# E70_AND_E79.net
KiCad netlist of a schematic drawn in Altium Designer
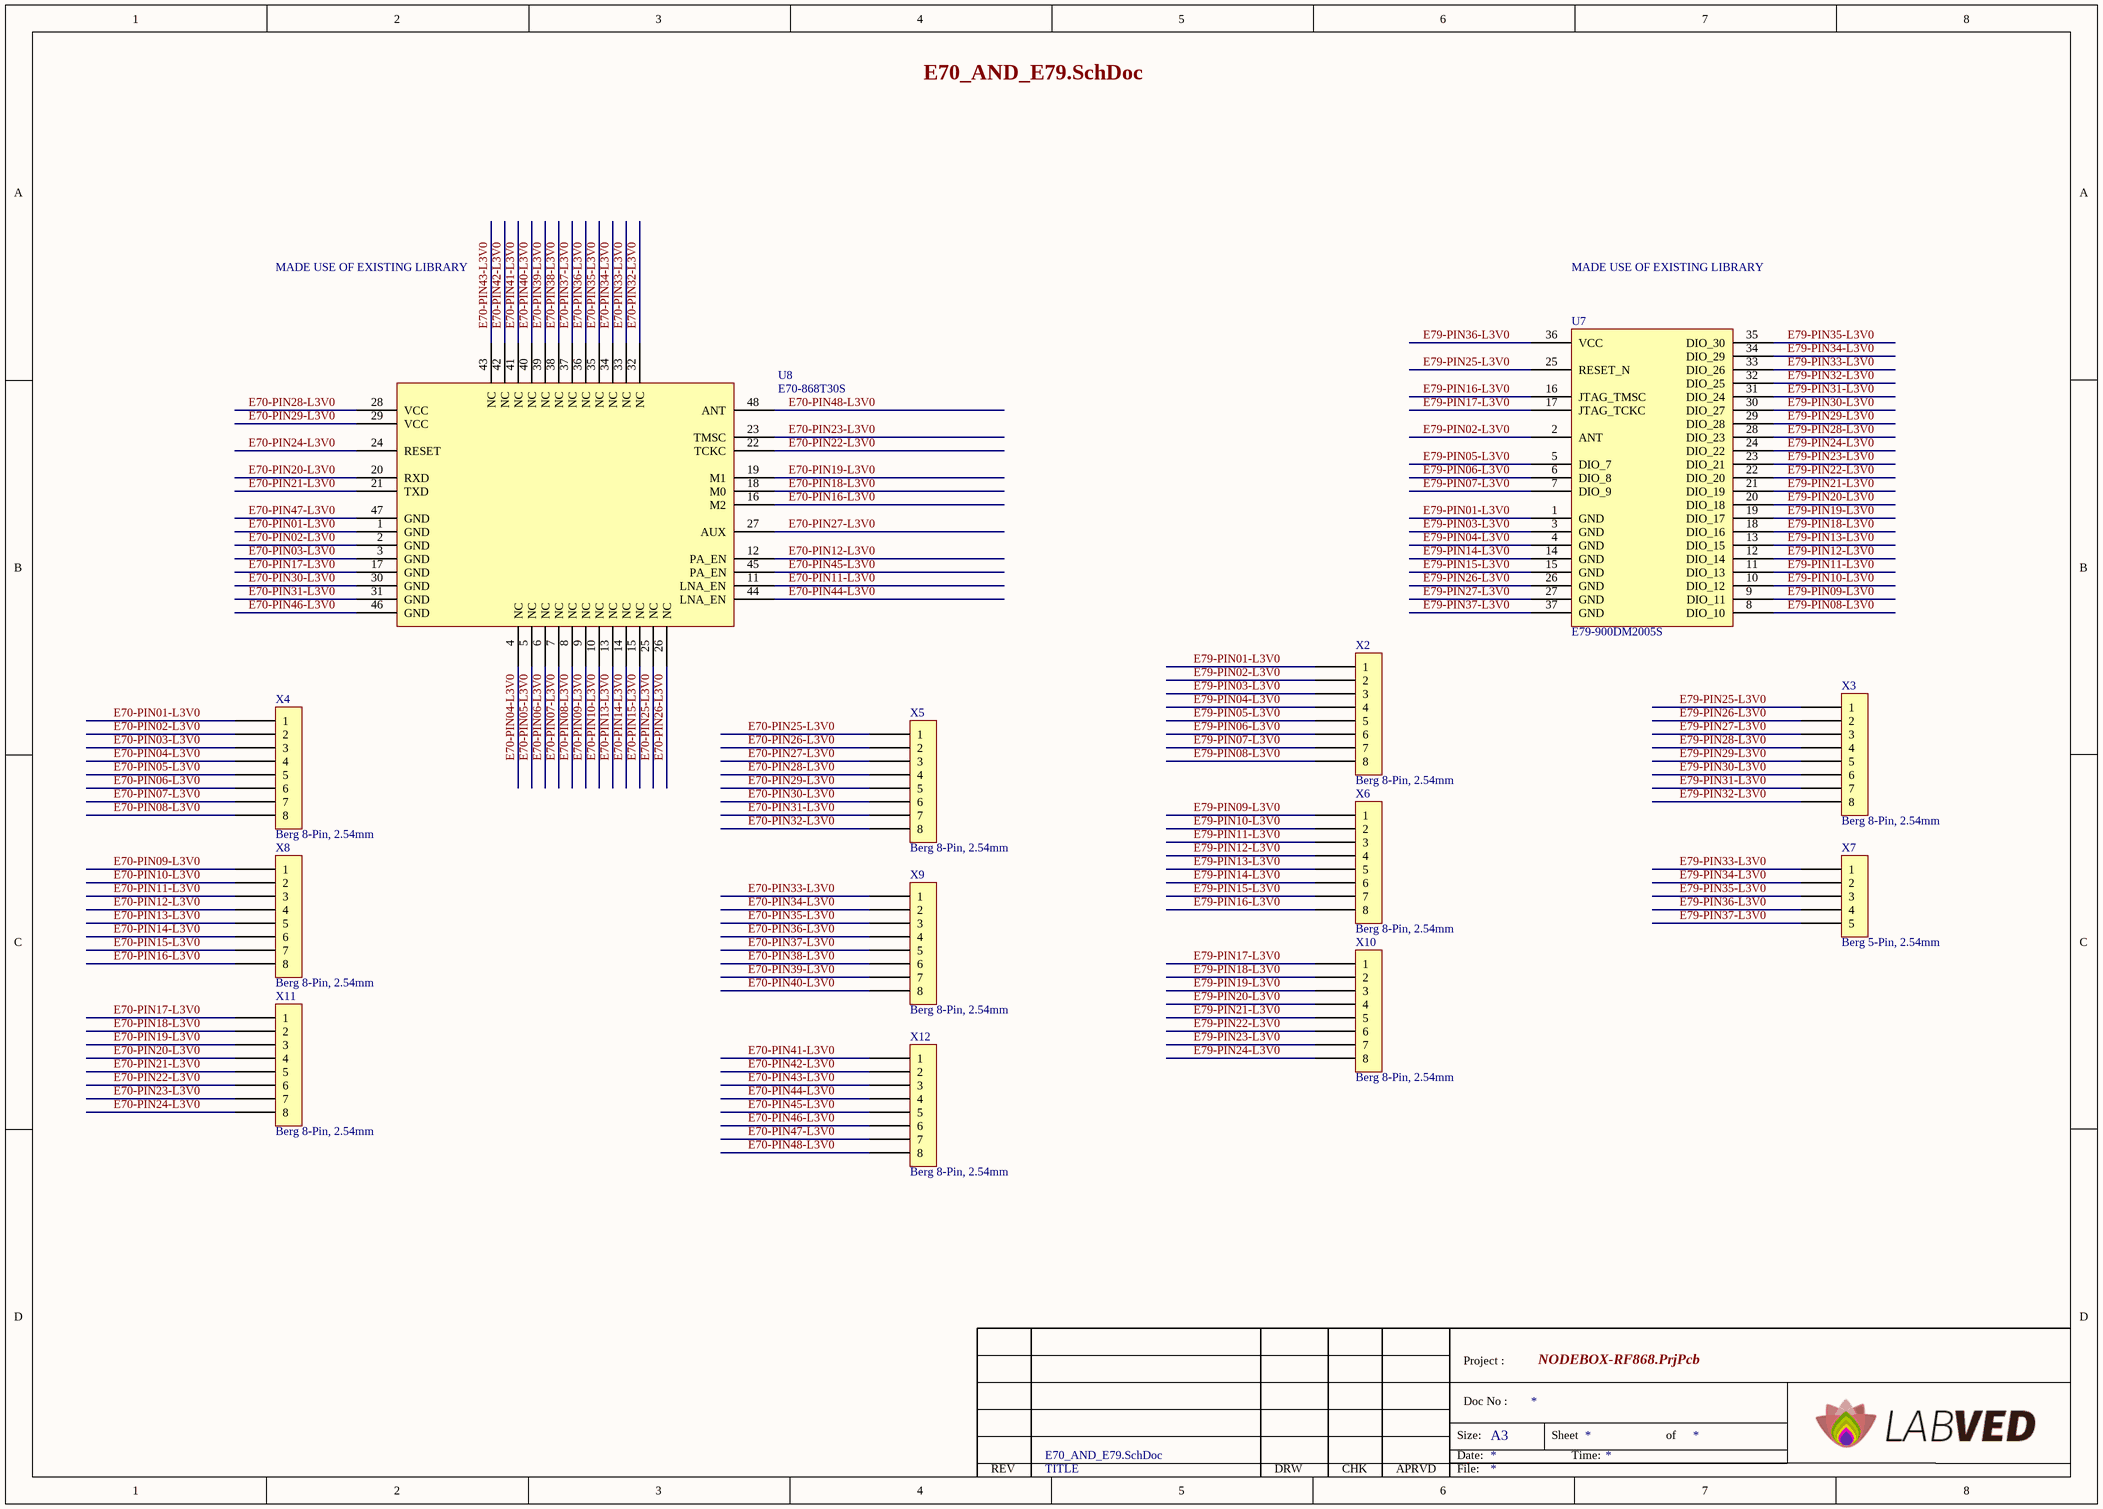
[diagram p0: E70_AND_E79.SchDoc]

(export (version "E")
  (design (tool "Eeschema 10.0.6"))
  (components
    (comp (ref "U7")
      (value "E79-900DM2005S")
      (footprint "E79-900DM2005S")
      (description "LORA MODULE")
      (libsource (lib "<Company> Vault") (part "E79-900DM2005S"))
    )
    (comp (ref "U8")
      (value "E70-868T30S")
      (footprint "E70-868T30S")
      (description "WIRELESS LORA MODULE")
      (libsource (lib "<Company> Vault") (part "E70-868T30S"))
    )
    (comp (ref "X2")
      (value "Berg 8-Pin, 2.54mm")
      (footprint "Berg 8-Pin, 2.54MM")
      (description "Berg 8-Pin, 2.54mm pitch")
      (libsource (lib "<Company> Vault") (part "Barrier Terminal Block, 8-Pin 8.25mm"))
    )
    (comp (ref "X3")
      (value "Berg 8-Pin, 2.54mm")
      (footprint "Berg 8-Pin, 2.54MM")
      (description "Berg 8-Pin, 2.54mm pitch")
      (libsource (lib "<Company> Vault") (part "Barrier Terminal Block, 8-Pin 8.25mm"))
    )
    (comp (ref "X4")
      (value "Berg 8-Pin, 2.54mm")
      (footprint "Berg 8-Pin, 2.54MM")
      (description "Berg 8-Pin, 2.54mm pitch")
      (libsource (lib "<Company> Vault") (part "Barrier Terminal Block, 8-Pin 8.25mm"))
    )
    (comp (ref "X5")
      (value "Berg 8-Pin, 2.54mm")
      (footprint "Berg 8-Pin, 2.54MM")
      (description "Berg 8-Pin, 2.54mm pitch")
      (libsource (lib "<Company> Vault") (part "Barrier Terminal Block, 8-Pin 8.25mm"))
    )
    (comp (ref "X6")
      (value "Berg 8-Pin, 2.54mm")
      (footprint "Berg 8-Pin, 2.54MM")
      (description "Berg 8-Pin, 2.54mm pitch")
      (libsource (lib "<Company> Vault") (part "Barrier Terminal Block, 8-Pin 8.25mm"))
    )
    (comp (ref "X7")
      (value "Berg 5-Pin, 2.54mm")
      (footprint "Berg 5-Pin, 2.54MM")
      (description "Berg 5-Pin, 2.54mm pitch")
      (libsource (lib "<Company> Vault") (part "Berg 5-Pin, 2.54mm"))
    )
    (comp (ref "X8")
      (value "Berg 8-Pin, 2.54mm")
      (footprint "Berg 8-Pin, 2.54MM")
      (description "Berg 8-Pin, 2.54mm pitch")
      (libsource (lib "<Company> Vault") (part "Barrier Terminal Block, 8-Pin 8.25mm"))
    )
    (comp (ref "X9")
      (value "Berg 8-Pin, 2.54mm")
      (footprint "Berg 8-Pin, 2.54MM")
      (description "Berg 8-Pin, 2.54mm pitch")
      (libsource (lib "<Company> Vault") (part "Barrier Terminal Block, 8-Pin 8.25mm"))
    )
    (comp (ref "X10")
      (value "Berg 8-Pin, 2.54mm")
      (footprint "Berg 8-Pin, 2.54MM")
      (description "Berg 8-Pin, 2.54mm pitch")
      (libsource (lib "<Company> Vault") (part "Barrier Terminal Block, 8-Pin 8.25mm"))
    )
    (comp (ref "X11")
      (value "Berg 8-Pin, 2.54mm")
      (footprint "Berg 8-Pin, 2.54MM")
      (description "Berg 8-Pin, 2.54mm pitch")
      (libsource (lib "<Company> Vault") (part "Barrier Terminal Block, 8-Pin 8.25mm"))
    )
    (comp (ref "X12")
      (value "Berg 8-Pin, 2.54mm")
      (footprint "Berg 8-Pin, 2.54MM")
      (description "Berg 8-Pin, 2.54mm pitch")
      (libsource (lib "<Company> Vault") (part "Barrier Terminal Block, 8-Pin 8.25mm"))
    )
  )
  (nets
    (net (code "1") (name "/E70-PIN01-L3V0") (class "Default")
      (node (ref "U8") (pin "1") (pinfunction "GND_1") (pintype "passive"))
      (node (ref "X4") (pin "1") (pinfunction "1_1") (pintype "passive"))
    )
    (net (code "2") (name "/E70-PIN02-L3V0") (class "Default")
      (node (ref "U8") (pin "2") (pinfunction "GND_2") (pintype "passive"))
      (node (ref "X4") (pin "2") (pinfunction "2_2") (pintype "passive"))
    )
    (net (code "3") (name "/E70-PIN03-L3V0") (class "Default")
      (node (ref "U8") (pin "3") (pinfunction "GND_3") (pintype "passive"))
      (node (ref "X4") (pin "3") (pinfunction "3_3") (pintype "passive"))
    )
    (net (code "4") (name "/E70-PIN04-L3V0") (class "Default")
      (node (ref "U8") (pin "4") (pinfunction "NC_4") (pintype "passive"))
      (node (ref "X4") (pin "4") (pinfunction "4_4") (pintype "passive"))
    )
    (net (code "5") (name "/E70-PIN05-L3V0") (class "Default")
      (node (ref "U8") (pin "5") (pinfunction "NC_5") (pintype "passive"))
      (node (ref "X4") (pin "5") (pinfunction "5_5") (pintype "passive"))
    )
    (net (code "6") (name "/E70-PIN06-L3V0") (class "Default")
      (node (ref "U8") (pin "6") (pinfunction "NC_6") (pintype "passive"))
      (node (ref "X4") (pin "6") (pinfunction "6_6") (pintype "passive"))
    )
    (net (code "7") (name "/E70-PIN07-L3V0") (class "Default")
      (node (ref "U8") (pin "7") (pinfunction "NC_7") (pintype "passive"))
      (node (ref "X4") (pin "7") (pinfunction "7_7") (pintype "passive"))
    )
    (net (code "8") (name "/E70-PIN08-L3V0") (class "Default")
      (node (ref "U8") (pin "8") (pinfunction "NC_8") (pintype "passive"))
      (node (ref "X4") (pin "8") (pinfunction "8_8") (pintype "passive"))
    )
    (net (code "9") (name "/E70-PIN09-L3V0") (class "Default")
      (node (ref "U8") (pin "9") (pinfunction "NC_9") (pintype "passive"))
      (node (ref "X8") (pin "1") (pinfunction "1_1") (pintype "passive"))
    )
    (net (code "10") (name "/E70-PIN10-L3V0") (class "Default")
      (node (ref "U8") (pin "10") (pinfunction "NC_10") (pintype "passive"))
      (node (ref "X8") (pin "2") (pinfunction "2_2") (pintype "passive"))
    )
    (net (code "11") (name "/E70-PIN11-L3V0") (class "Default")
      (node (ref "U8") (pin "11") (pinfunction "LNA_EN_11") (pintype "passive"))
      (node (ref "X8") (pin "3") (pinfunction "3_3") (pintype "passive"))
    )
    (net (code "12") (name "/E70-PIN12-L3V0") (class "Default")
      (node (ref "U8") (pin "12") (pinfunction "PA_EN_12") (pintype "passive"))
      (node (ref "X8") (pin "4") (pinfunction "4_4") (pintype "passive"))
    )
    (net (code "13") (name "/E70-PIN13-L3V0") (class "Default")
      (node (ref "U8") (pin "13") (pinfunction "NC_13") (pintype "passive"))
      (node (ref "X8") (pin "5") (pinfunction "5_5") (pintype "passive"))
    )
    (net (code "14") (name "/E70-PIN14-L3V0") (class "Default")
      (node (ref "U8") (pin "14") (pinfunction "NC_14") (pintype "passive"))
      (node (ref "X8") (pin "6") (pinfunction "6_6") (pintype "passive"))
    )
    (net (code "15") (name "/E70-PIN15-L3V0") (class "Default")
      (node (ref "U8") (pin "15") (pinfunction "NC_15") (pintype "passive"))
      (node (ref "X8") (pin "7") (pinfunction "7_7") (pintype "passive"))
    )
    (net (code "16") (name "/E70-PIN16-L3V0") (class "Default")
      (node (ref "U8") (pin "16") (pinfunction "M2_16") (pintype "passive"))
      (node (ref "X8") (pin "8") (pinfunction "8_8") (pintype "passive"))
    )
    (net (code "17") (name "/E70-PIN17-L3V0") (class "Default")
      (node (ref "U8") (pin "17") (pinfunction "GND_17") (pintype "passive"))
      (node (ref "X11") (pin "1") (pinfunction "1_1") (pintype "passive"))
    )
    (net (code "18") (name "/E70-PIN18-L3V0") (class "Default")
      (node (ref "U8") (pin "18") (pinfunction "M0_18") (pintype "passive"))
      (node (ref "X11") (pin "2") (pinfunction "2_2") (pintype "passive"))
    )
    (net (code "19") (name "/E70-PIN19-L3V0") (class "Default")
      (node (ref "U8") (pin "19") (pinfunction "M1_19") (pintype "passive"))
      (node (ref "X11") (pin "3") (pinfunction "3_3") (pintype "passive"))
    )
    (net (code "20") (name "/E70-PIN20-L3V0") (class "Default")
      (node (ref "U8") (pin "20") (pinfunction "RXD_20") (pintype "passive"))
      (node (ref "X11") (pin "4") (pinfunction "4_4") (pintype "passive"))
    )
    (net (code "21") (name "/E70-PIN21-L3V0") (class "Default")
      (node (ref "U8") (pin "21") (pinfunction "TXD_21") (pintype "passive"))
      (node (ref "X11") (pin "5") (pinfunction "5_5") (pintype "passive"))
    )
    (net (code "22") (name "/E70-PIN22-L3V0") (class "Default")
      (node (ref "U8") (pin "22") (pinfunction "TCKC_22") (pintype "passive"))
      (node (ref "X11") (pin "6") (pinfunction "6_6") (pintype "passive"))
    )
    (net (code "23") (name "/E70-PIN23-L3V0") (class "Default")
      (node (ref "U8") (pin "23") (pinfunction "TMSC_23") (pintype "passive"))
      (node (ref "X11") (pin "7") (pinfunction "7_7") (pintype "passive"))
    )
    (net (code "24") (name "/E70-PIN24-L3V0") (class "Default")
      (node (ref "U8") (pin "24") (pinfunction "RESET_24") (pintype "passive"))
      (node (ref "X11") (pin "8") (pinfunction "8_8") (pintype "passive"))
    )
    (net (code "25") (name "/E70-PIN25-L3V0") (class "Default")
      (node (ref "U8") (pin "25") (pinfunction "NC_25") (pintype "passive"))
      (node (ref "X5") (pin "1") (pinfunction "1_1") (pintype "passive"))
    )
    (net (code "26") (name "/E70-PIN26-L3V0") (class "Default")
      (node (ref "U8") (pin "26") (pinfunction "NC_26") (pintype "passive"))
      (node (ref "X5") (pin "2") (pinfunction "2_2") (pintype "passive"))
    )
    (net (code "27") (name "/E70-PIN27-L3V0") (class "Default")
      (node (ref "U8") (pin "27") (pinfunction "AUX_27") (pintype "passive"))
      (node (ref "X5") (pin "3") (pinfunction "3_3") (pintype "passive"))
    )
    (net (code "28") (name "/E70-PIN28-L3V0") (class "Default")
      (node (ref "U8") (pin "28") (pinfunction "VCC_28") (pintype "passive"))
      (node (ref "X5") (pin "4") (pinfunction "4_4") (pintype "passive"))
    )
    (net (code "29") (name "/E70-PIN29-L3V0") (class "Default")
      (node (ref "U8") (pin "29") (pinfunction "VCC_29") (pintype "passive"))
      (node (ref "X5") (pin "5") (pinfunction "5_5") (pintype "passive"))
    )
    (net (code "30") (name "/E70-PIN30-L3V0") (class "Default")
      (node (ref "U8") (pin "30") (pinfunction "GND_30") (pintype "passive"))
      (node (ref "X5") (pin "6") (pinfunction "6_6") (pintype "passive"))
    )
    (net (code "31") (name "/E70-PIN31-L3V0") (class "Default")
      (node (ref "U8") (pin "31") (pinfunction "GND_31") (pintype "passive"))
      (node (ref "X5") (pin "7") (pinfunction "7_7") (pintype "passive"))
    )
    (net (code "32") (name "/E70-PIN32-L3V0") (class "Default")
      (node (ref "U8") (pin "32") (pinfunction "NC_32") (pintype "passive"))
      (node (ref "X5") (pin "8") (pinfunction "8_8") (pintype "passive"))
    )
    (net (code "33") (name "/E70-PIN33-L3V0") (class "Default")
      (node (ref "U8") (pin "33") (pinfunction "NC_33") (pintype "passive"))
      (node (ref "X9") (pin "1") (pinfunction "1_1") (pintype "passive"))
    )
    (net (code "34") (name "/E70-PIN34-L3V0") (class "Default")
      (node (ref "U8") (pin "34") (pinfunction "NC_34") (pintype "passive"))
      (node (ref "X9") (pin "2") (pinfunction "2_2") (pintype "passive"))
    )
    (net (code "35") (name "/E70-PIN35-L3V0") (class "Default")
      (node (ref "U8") (pin "35") (pinfunction "NC_35") (pintype "passive"))
      (node (ref "X9") (pin "3") (pinfunction "3_3") (pintype "passive"))
    )
    (net (code "36") (name "/E70-PIN36-L3V0") (class "Default")
      (node (ref "U8") (pin "36") (pinfunction "NC_36") (pintype "passive"))
      (node (ref "X9") (pin "4") (pinfunction "4_4") (pintype "passive"))
    )
    (net (code "37") (name "/E70-PIN37-L3V0") (class "Default")
      (node (ref "U8") (pin "37") (pinfunction "NC_37") (pintype "passive"))
      (node (ref "X9") (pin "5") (pinfunction "5_5") (pintype "passive"))
    )
    (net (code "38") (name "/E70-PIN38-L3V0") (class "Default")
      (node (ref "U8") (pin "38") (pinfunction "NC_38") (pintype "passive"))
      (node (ref "X9") (pin "6") (pinfunction "6_6") (pintype "passive"))
    )
    (net (code "39") (name "/E70-PIN39-L3V0") (class "Default")
      (node (ref "U8") (pin "39") (pinfunction "NC_39") (pintype "passive"))
      (node (ref "X9") (pin "7") (pinfunction "7_7") (pintype "passive"))
    )
    (net (code "40") (name "/E70-PIN40-L3V0") (class "Default")
      (node (ref "U8") (pin "40") (pinfunction "NC_40") (pintype "passive"))
      (node (ref "X9") (pin "8") (pinfunction "8_8") (pintype "passive"))
    )
    (net (code "41") (name "/E70-PIN41-L3V0") (class "Default")
      (node (ref "U8") (pin "41") (pinfunction "NC_41") (pintype "passive"))
      (node (ref "X12") (pin "1") (pinfunction "1_1") (pintype "passive"))
    )
    (net (code "42") (name "/E70-PIN42-L3V0") (class "Default")
      (node (ref "U8") (pin "42") (pinfunction "NC_42") (pintype "passive"))
      (node (ref "X12") (pin "2") (pinfunction "2_2") (pintype "passive"))
    )
    (net (code "43") (name "/E70-PIN43-L3V0") (class "Default")
      (node (ref "U8") (pin "43") (pinfunction "NC_43") (pintype "passive"))
      (node (ref "X12") (pin "3") (pinfunction "3_3") (pintype "passive"))
    )
    (net (code "44") (name "/E70-PIN44-L3V0") (class "Default")
      (node (ref "U8") (pin "44") (pinfunction "LNA_EN_44") (pintype "passive"))
      (node (ref "X12") (pin "4") (pinfunction "4_4") (pintype "passive"))
    )
    (net (code "45") (name "/E70-PIN45-L3V0") (class "Default")
      (node (ref "U8") (pin "45") (pinfunction "PA_EN_45") (pintype "passive"))
      (node (ref "X12") (pin "5") (pinfunction "5_5") (pintype "passive"))
    )
    (net (code "46") (name "/E70-PIN46-L3V0") (class "Default")
      (node (ref "U8") (pin "46") (pinfunction "GND_46") (pintype "passive"))
      (node (ref "X12") (pin "6") (pinfunction "6_6") (pintype "passive"))
    )
    (net (code "47") (name "/E70-PIN47-L3V0") (class "Default")
      (node (ref "U8") (pin "47") (pinfunction "GND_47") (pintype "passive"))
      (node (ref "X12") (pin "7") (pinfunction "7_7") (pintype "passive"))
    )
    (net (code "48") (name "/E70-PIN48-L3V0") (class "Default")
      (node (ref "U8") (pin "48") (pinfunction "ANT_48") (pintype "passive"))
      (node (ref "X12") (pin "8") (pinfunction "8_8") (pintype "passive"))
    )
    (net (code "49") (name "/E79-PIN01-L3V0") (class "Default")
      (node (ref "U7") (pin "1") (pinfunction "GND_1") (pintype "passive"))
      (node (ref "X2") (pin "1") (pinfunction "1_1") (pintype "passive"))
    )
    (net (code "50") (name "/E79-PIN02-L3V0") (class "Default")
      (node (ref "U7") (pin "2") (pinfunction "ANT_2") (pintype "passive"))
      (node (ref "X2") (pin "2") (pinfunction "2_2") (pintype "passive"))
    )
    (net (code "51") (name "/E79-PIN03-L3V0") (class "Default")
      (node (ref "U7") (pin "3") (pinfunction "GND_3") (pintype "passive"))
      (node (ref "X2") (pin "3") (pinfunction "3_3") (pintype "passive"))
    )
    (net (code "52") (name "/E79-PIN04-L3V0") (class "Default")
      (node (ref "U7") (pin "4") (pinfunction "GND_4") (pintype "passive"))
      (node (ref "X2") (pin "4") (pinfunction "4_4") (pintype "passive"))
    )
    (net (code "53") (name "/E79-PIN05-L3V0") (class "Default")
      (node (ref "U7") (pin "5") (pinfunction "DIO_7_5") (pintype "passive"))
      (node (ref "X2") (pin "5") (pinfunction "5_5") (pintype "passive"))
    )
    (net (code "54") (name "/E79-PIN06-L3V0") (class "Default")
      (node (ref "U7") (pin "6") (pinfunction "DIO_8_6") (pintype "passive"))
      (node (ref "X2") (pin "6") (pinfunction "6_6") (pintype "passive"))
    )
    (net (code "55") (name "/E79-PIN07-L3V0") (class "Default")
      (node (ref "U7") (pin "7") (pinfunction "DIO_9_7") (pintype "passive"))
      (node (ref "X2") (pin "7") (pinfunction "7_7") (pintype "passive"))
    )
    (net (code "56") (name "/E79-PIN08-L3V0") (class "Default")
      (node (ref "U7") (pin "8") (pinfunction "DIO_10_8") (pintype "passive"))
      (node (ref "X2") (pin "8") (pinfunction "8_8") (pintype "passive"))
    )
    (net (code "57") (name "/E79-PIN09-L3V0") (class "Default")
      (node (ref "U7") (pin "9") (pinfunction "DIO_11_9") (pintype "passive"))
      (node (ref "X6") (pin "1") (pinfunction "1_1") (pintype "passive"))
    )
    (net (code "58") (name "/E79-PIN10-L3V0") (class "Default")
      (node (ref "U7") (pin "10") (pinfunction "DIO_12_10") (pintype "passive"))
      (node (ref "X6") (pin "2") (pinfunction "2_2") (pintype "passive"))
    )
    (net (code "59") (name "/E79-PIN11-L3V0") (class "Default")
      (node (ref "U7") (pin "11") (pinfunction "DIO_13_11") (pintype "passive"))
      (node (ref "X6") (pin "3") (pinfunction "3_3") (pintype "passive"))
    )
    (net (code "60") (name "/E79-PIN12-L3V0") (class "Default")
      (node (ref "U7") (pin "12") (pinfunction "DIO_14_12") (pintype "passive"))
      (node (ref "X6") (pin "4") (pinfunction "4_4") (pintype "passive"))
    )
    (net (code "61") (name "/E79-PIN13-L3V0") (class "Default")
      (node (ref "U7") (pin "13") (pinfunction "DIO_15_13") (pintype "passive"))
      (node (ref "X6") (pin "5") (pinfunction "5_5") (pintype "passive"))
    )
    (net (code "62") (name "/E79-PIN14-L3V0") (class "Default")
      (node (ref "U7") (pin "14") (pinfunction "GND_14") (pintype "passive"))
      (node (ref "X6") (pin "6") (pinfunction "6_6") (pintype "passive"))
    )
    (net (code "63") (name "/E79-PIN15-L3V0") (class "Default")
      (node (ref "U7") (pin "15") (pinfunction "GND_15") (pintype "passive"))
      (node (ref "X6") (pin "7") (pinfunction "7_7") (pintype "passive"))
    )
    (net (code "64") (name "/E79-PIN16-L3V0") (class "Default")
      (node (ref "U7") (pin "16") (pinfunction "JTAG_TMSC_16") (pintype "passive"))
      (node (ref "X6") (pin "8") (pinfunction "8_8") (pintype "passive"))
    )
    (net (code "65") (name "/E79-PIN17-L3V0") (class "Default")
      (node (ref "U7") (pin "17") (pinfunction "JTAG_TCKC_17") (pintype "passive"))
      (node (ref "X10") (pin "1") (pinfunction "1_1") (pintype "passive"))
    )
    (net (code "66") (name "/E79-PIN18-L3V0") (class "Default")
      (node (ref "U7") (pin "18") (pinfunction "DIO_16_18") (pintype "passive"))
      (node (ref "X10") (pin "2") (pinfunction "2_2") (pintype "passive"))
    )
    (net (code "67") (name "/E79-PIN19-L3V0") (class "Default")
      (node (ref "U7") (pin "19") (pinfunction "DIO_17_19") (pintype "passive"))
      (node (ref "X10") (pin "3") (pinfunction "3_3") (pintype "passive"))
    )
    (net (code "68") (name "/E79-PIN20-L3V0") (class "Default")
      (node (ref "U7") (pin "20") (pinfunction "DIO_18_20") (pintype "passive"))
      (node (ref "X10") (pin "4") (pinfunction "4_4") (pintype "passive"))
    )
    (net (code "69") (name "/E79-PIN21-L3V0") (class "Default")
      (node (ref "U7") (pin "21") (pinfunction "DIO_19_21") (pintype "passive"))
      (node (ref "X10") (pin "5") (pinfunction "5_5") (pintype "passive"))
    )
    (net (code "70") (name "/E79-PIN22-L3V0") (class "Default")
      (node (ref "U7") (pin "22") (pinfunction "DIO_20_22") (pintype "passive"))
      (node (ref "X10") (pin "6") (pinfunction "6_6") (pintype "passive"))
    )
    (net (code "71") (name "/E79-PIN23-L3V0") (class "Default")
      (node (ref "U7") (pin "23") (pinfunction "DIO_21_23") (pintype "passive"))
      (node (ref "X10") (pin "7") (pinfunction "7_7") (pintype "passive"))
    )
    (net (code "72") (name "/E79-PIN24-L3V0") (class "Default")
      (node (ref "U7") (pin "24") (pinfunction "DIO_22_24") (pintype "passive"))
      (node (ref "X10") (pin "8") (pinfunction "8_8") (pintype "passive"))
    )
    (net (code "73") (name "/E79-PIN25-L3V0") (class "Default")
      (node (ref "U7") (pin "25") (pinfunction "RESET_N_25") (pintype "passive"))
      (node (ref "X3") (pin "1") (pinfunction "1_1") (pintype "passive"))
    )
    (net (code "74") (name "/E79-PIN26-L3V0") (class "Default")
      (node (ref "U7") (pin "26") (pinfunction "GND_26") (pintype "passive"))
      (node (ref "X3") (pin "2") (pinfunction "2_2") (pintype "passive"))
    )
    (net (code "75") (name "/E79-PIN27-L3V0") (class "Default")
      (node (ref "U7") (pin "27") (pinfunction "GND_27") (pintype "passive"))
      (node (ref "X3") (pin "3") (pinfunction "3_3") (pintype "passive"))
    )
    (net (code "76") (name "/E79-PIN28-L3V0") (class "Default")
      (node (ref "U7") (pin "28") (pinfunction "DIO_23_28") (pintype "passive"))
      (node (ref "X3") (pin "4") (pinfunction "4_4") (pintype "passive"))
    )
    (net (code "77") (name "/E79-PIN29-L3V0") (class "Default")
      (node (ref "U7") (pin "29") (pinfunction "DIO_28_29") (pintype "passive"))
      (node (ref "X3") (pin "5") (pinfunction "5_5") (pintype "passive"))
    )
    (net (code "78") (name "/E79-PIN30-L3V0") (class "Default")
      (node (ref "U7") (pin "30") (pinfunction "DIO_27_30") (pintype "passive"))
      (node (ref "X3") (pin "6") (pinfunction "6_6") (pintype "passive"))
    )
    (net (code "79") (name "/E79-PIN31-L3V0") (class "Default")
      (node (ref "U7") (pin "31") (pinfunction "DIO_24_31") (pintype "passive"))
      (node (ref "X3") (pin "7") (pinfunction "7_7") (pintype "passive"))
    )
    (net (code "80") (name "/E79-PIN32-L3V0") (class "Default")
      (node (ref "U7") (pin "32") (pinfunction "DIO_25_32") (pintype "passive"))
      (node (ref "X3") (pin "8") (pinfunction "8_8") (pintype "passive"))
    )
    (net (code "81") (name "/E79-PIN33-L3V0") (class "Default")
      (node (ref "U7") (pin "33") (pinfunction "DIO_26_33") (pintype "passive"))
      (node (ref "X7") (pin "1") (pinfunction "1_1") (pintype "passive"))
    )
    (net (code "82") (name "/E79-PIN34-L3V0") (class "Default")
      (node (ref "U7") (pin "34") (pinfunction "DIO_29_34") (pintype "passive"))
      (node (ref "X7") (pin "2") (pinfunction "2_2") (pintype "passive"))
    )
    (net (code "83") (name "/E79-PIN35-L3V0") (class "Default")
      (node (ref "U7") (pin "35") (pinfunction "DIO_30_35") (pintype "passive"))
      (node (ref "X7") (pin "3") (pinfunction "3_3") (pintype "passive"))
    )
    (net (code "84") (name "/E79-PIN36-L3V0") (class "Default")
      (node (ref "U7") (pin "36") (pinfunction "VCC_36") (pintype "passive"))
      (node (ref "X7") (pin "4") (pinfunction "4_4") (pintype "passive"))
    )
    (net (code "85") (name "/E79-PIN37-L3V0") (class "Default")
      (node (ref "U7") (pin "37") (pinfunction "GND_37") (pintype "passive"))
      (node (ref "X7") (pin "5") (pinfunction "5_5") (pintype "passive"))
    )
  )
)
